# Esquema.net
KiCad netlist of a schematic drawn in EAGLE
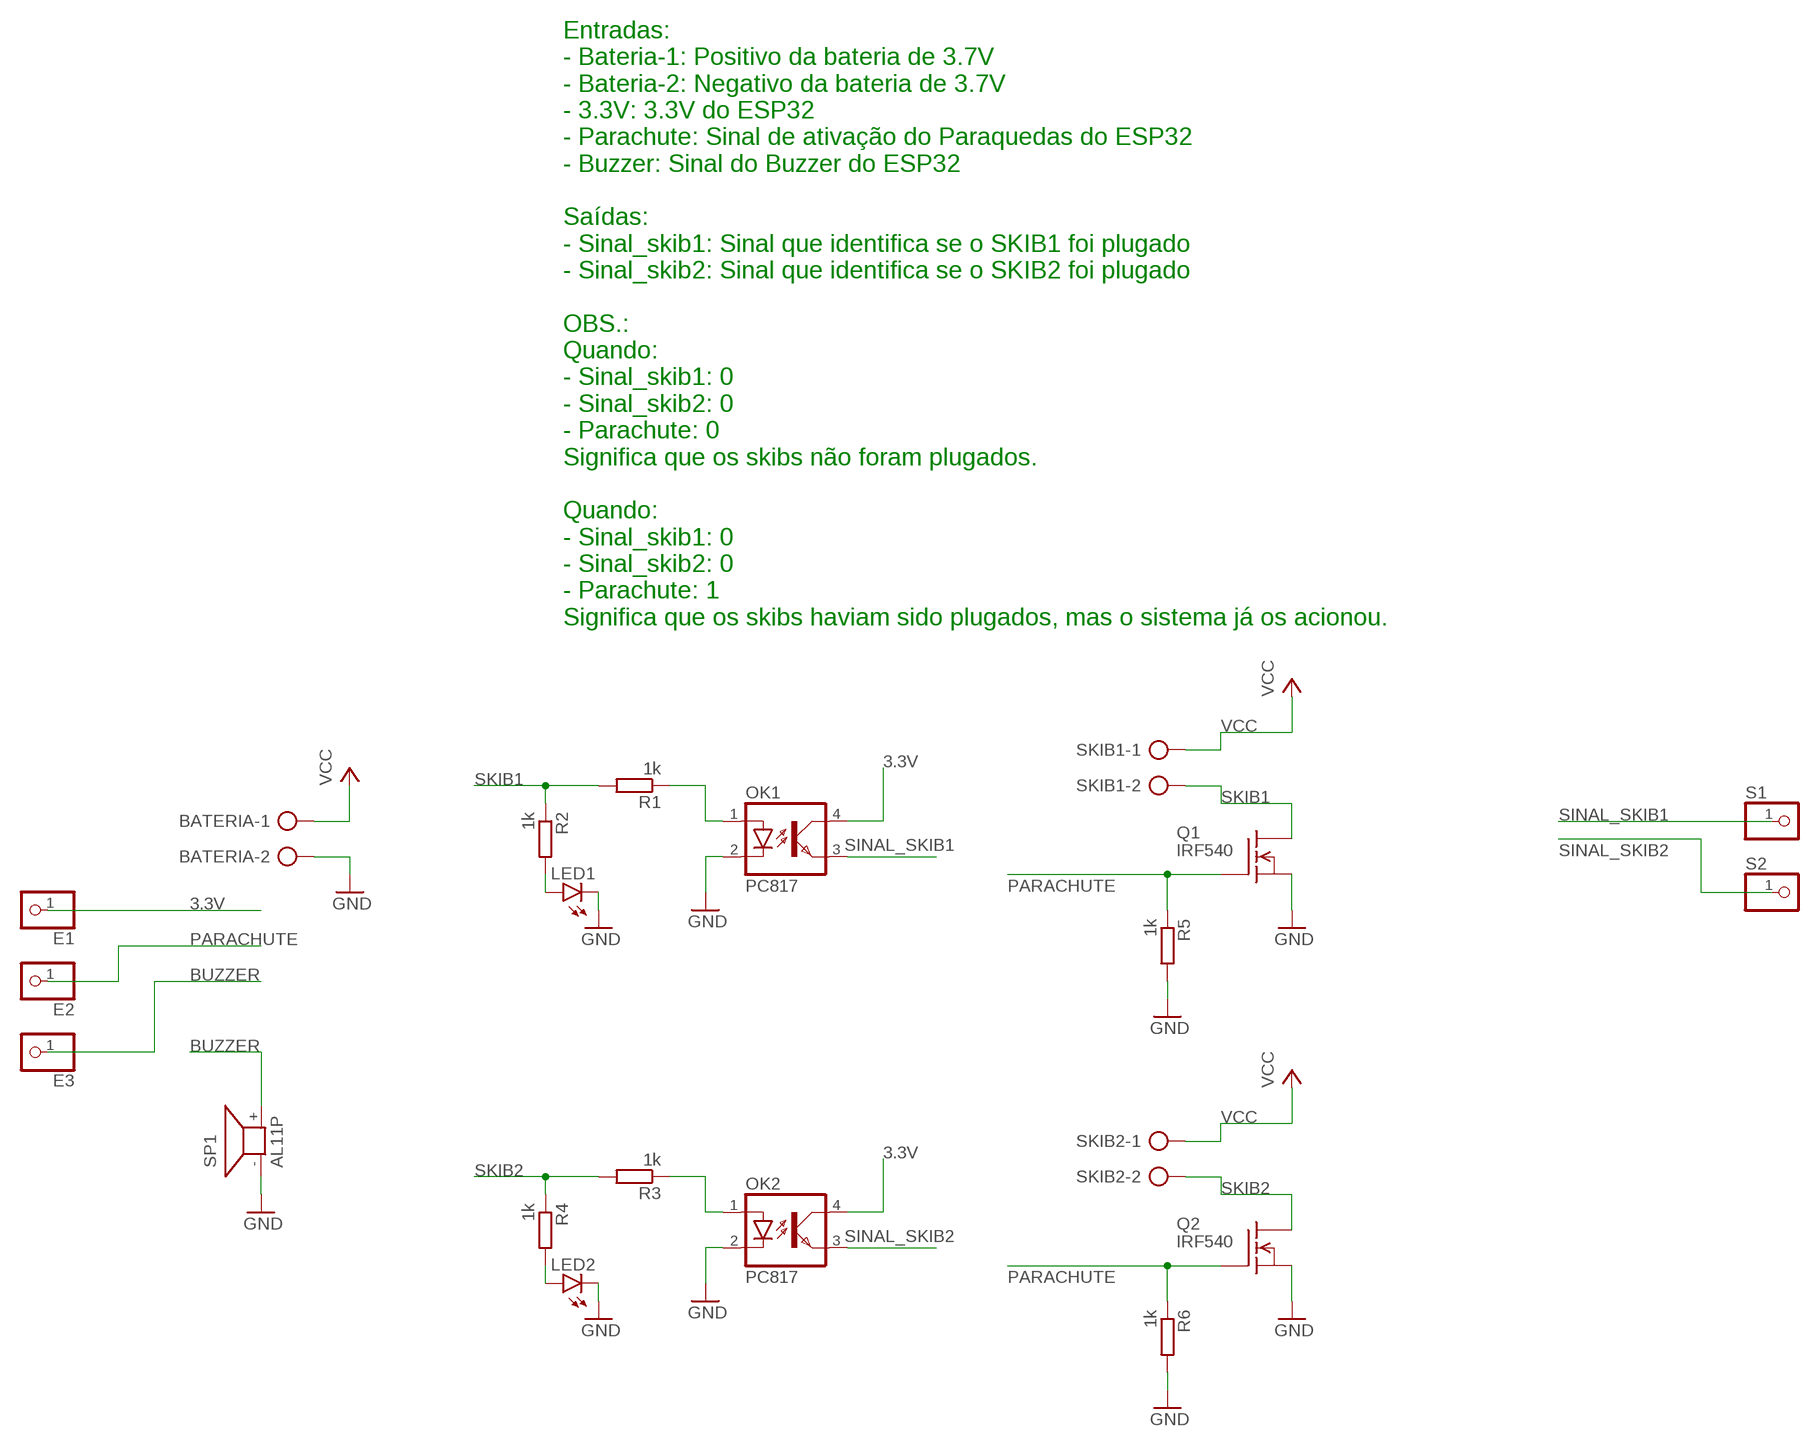
[diagram p0: schematic, sheet 1]

(export (version "E")
  (design (tool "Eeschema 10.0.6"))
  (components
    (comp (ref "BATERIA")
      (value "AK500/2-H")
      (footprint "eagle-import:AK500_2-H")
      (libsource (lib "eagle-import") (part "AK500/2-H"))
    )
    (comp (ref "E1")
      (value "PINHD-1X1")
      (footprint "eagle-import:1X01")
      (libsource (lib "eagle-import") (part "PINHD-1X1"))
    )
    (comp (ref "E2")
      (value "PINHD-1X1")
      (footprint "eagle-import:1X01")
      (libsource (lib "eagle-import") (part "PINHD-1X1"))
    )
    (comp (ref "E3")
      (value "PINHD-1X1")
      (footprint "eagle-import:1X01")
      (libsource (lib "eagle-import") (part "PINHD-1X1"))
    )
    (comp (ref "LED1")
      (value "LED5MM")
      (footprint "eagle-import:LED5MM")
      (libsource (lib "eagle-import") (part "LED5MM"))
    )
    (comp (ref "LED2")
      (value "LED5MM")
      (footprint "eagle-import:LED5MM")
      (libsource (lib "eagle-import") (part "LED5MM"))
    )
    (comp (ref "OK1")
      (value "PC817")
      (footprint "eagle-import:DIL04")
      (fields (field (name "MPN") "PC817X4J000F"))
      (libsource (lib "eagle-import") (part "PC817"))
    )
    (comp (ref "OK2")
      (value "PC817")
      (footprint "eagle-import:DIL04")
      (fields (field (name "MPN") "PC817X4J000F"))
      (libsource (lib "eagle-import") (part "PC817"))
    )
    (comp (ref "Q1")
      (value "IRF540")
      (footprint "eagle-import:TO220")
      (libsource (lib "eagle-import") (part "IRF540"))
    )
    (comp (ref "Q2")
      (value "IRF540")
      (footprint "eagle-import:TO220")
      (libsource (lib "eagle-import") (part "IRF540"))
    )
    (comp (ref "R1")
      (value "1k")
      (footprint "eagle-import:0207_10")
      (libsource (lib "eagle-import") (part "R-EU_0207/10"))
    )
    (comp (ref "R2")
      (value "1k")
      (footprint "eagle-import:0207_10")
      (libsource (lib "eagle-import") (part "R-EU_0207/10"))
    )
    (comp (ref "R3")
      (value "1k")
      (footprint "eagle-import:0207_10")
      (libsource (lib "eagle-import") (part "R-EU_0207/10"))
    )
    (comp (ref "R4")
      (value "1k")
      (footprint "eagle-import:0207_10")
      (libsource (lib "eagle-import") (part "R-EU_0207/10"))
    )
    (comp (ref "R5")
      (value "1k")
      (footprint "eagle-import:0207_10")
      (libsource (lib "eagle-import") (part "R-EU_0207/10"))
    )
    (comp (ref "R6")
      (value "1k")
      (footprint "eagle-import:0207_10")
      (libsource (lib "eagle-import") (part "R-EU_0207/10"))
    )
    (comp (ref "S1")
      (value "PINHD-1X1")
      (footprint "eagle-import:1X01")
      (libsource (lib "eagle-import") (part "PINHD-1X1"))
    )
    (comp (ref "S2")
      (value "PINHD-1X1")
      (footprint "eagle-import:1X01")
      (libsource (lib "eagle-import") (part "PINHD-1X1"))
    )
    (comp (ref "SKIB1")
      (value "AK500/2-H")
      (footprint "eagle-import:AK500_2-H")
      (libsource (lib "eagle-import") (part "AK500/2-H"))
    )
    (comp (ref "SKIB2")
      (value "AK500/2-H")
      (footprint "eagle-import:AK500_2-H")
      (libsource (lib "eagle-import") (part "AK500/2-H"))
    )
    (comp (ref "SP1")
      (value "AL11P")
      (footprint "eagle-import:AL11P")
      (libsource (lib "eagle-import") (part "AL11P"))
    )
  )
  (nets
    (net (code "1") (name "/3.3V") (class "Default")
      (node (ref "E1") (pin "1") (pinfunction "1_1") (pintype "passive"))
      (node (ref "OK1") (pin "4") (pinfunction "COL_4") (pintype "passive"))
      (node (ref "OK2") (pin "4") (pinfunction "COL_4") (pintype "passive"))
    )
    (net (code "2") (name "/BUZZER") (class "Default")
      (node (ref "E3") (pin "1") (pinfunction "1_1") (pintype "passive"))
      (node (ref "SP1") (pin "+") (pinfunction "2_+") (pintype "passive"))
    )
    (net (code "3") (name "/PARACHUTE") (class "Default")
      (node (ref "E2") (pin "1") (pinfunction "1_1") (pintype "passive"))
      (node (ref "Q1") (pin "1") (pinfunction "G_1") (pintype "passive"))
      (node (ref "Q2") (pin "1") (pinfunction "G_1") (pintype "passive"))
      (node (ref "R5") (pin "1") (pinfunction "1_1") (pintype "passive"))
      (node (ref "R6") (pin "1") (pinfunction "1_1") (pintype "passive"))
    )
    (net (code "4") (name "/SINAL_SKIB1") (class "Default")
      (node (ref "OK1") (pin "3") (pinfunction "EMIT_3") (pintype "passive"))
      (node (ref "S1") (pin "1") (pinfunction "1_1") (pintype "passive"))
    )
    (net (code "5") (name "/SINAL_SKIB2") (class "Default")
      (node (ref "OK2") (pin "3") (pinfunction "EMIT_3") (pintype "passive"))
      (node (ref "S2") (pin "1") (pinfunction "1_1") (pintype "passive"))
    )
    (net (code "6") (name "/SKIB1") (class "Default")
      (node (ref "Q1") (pin "2") (pinfunction "D_2") (pintype "passive"))
      (node (ref "R1") (pin "2") (pinfunction "2_2") (pintype "passive"))
      (node (ref "R2") (pin "1") (pinfunction "1_1") (pintype "passive"))
      (node (ref "SKIB1") (pin "2") (pinfunction "KL_2") (pintype "passive"))
    )
    (net (code "7") (name "/SKIB2") (class "Default")
      (node (ref "Q2") (pin "2") (pinfunction "D_2") (pintype "passive"))
      (node (ref "R3") (pin "2") (pinfunction "2_2") (pintype "passive"))
      (node (ref "R4") (pin "1") (pinfunction "1_1") (pintype "passive"))
      (node (ref "SKIB2") (pin "2") (pinfunction "KL_2") (pintype "passive"))
    )
    (net (code "8") (name "GND") (class "Default")
      (node (ref "BATERIA") (pin "2") (pinfunction "KL_2") (pintype "passive"))
      (node (ref "LED1") (pin "K") (pinfunction "C_K") (pintype "passive"))
      (node (ref "LED2") (pin "K") (pinfunction "C_K") (pintype "passive"))
      (node (ref "OK1") (pin "2") (pinfunction "C_2") (pintype "passive"))
      (node (ref "OK2") (pin "2") (pinfunction "C_2") (pintype "passive"))
      (node (ref "Q1") (pin "3") (pinfunction "S_3") (pintype "passive"))
      (node (ref "Q2") (pin "3") (pinfunction "S_3") (pintype "passive"))
      (node (ref "R5") (pin "2") (pinfunction "2_2") (pintype "passive"))
      (node (ref "R6") (pin "2") (pinfunction "2_2") (pintype "passive"))
      (node (ref "SP1") (pin "-") (pinfunction "1_-") (pintype "passive"))
    )
    (net (code "9") (name "Net-(LED1-PadA)") (class "Default")
      (node (ref "LED1") (pin "A") (pinfunction "A_A") (pintype "passive"))
      (node (ref "R2") (pin "2") (pinfunction "2_2") (pintype "passive"))
    )
    (net (code "10") (name "Net-(LED2-PadA)") (class "Default")
      (node (ref "LED2") (pin "A") (pinfunction "A_A") (pintype "passive"))
      (node (ref "R4") (pin "2") (pinfunction "2_2") (pintype "passive"))
    )
    (net (code "11") (name "Net-(OK1-A)") (class "Default")
      (node (ref "OK1") (pin "1") (pinfunction "A_1") (pintype "passive"))
      (node (ref "R1") (pin "1") (pinfunction "1_1") (pintype "passive"))
    )
    (net (code "12") (name "Net-(OK2-A)") (class "Default")
      (node (ref "OK2") (pin "1") (pinfunction "A_1") (pintype "passive"))
      (node (ref "R3") (pin "1") (pinfunction "1_1") (pintype "passive"))
    )
    (net (code "13") (name "VCC") (class "Default")
      (node (ref "BATERIA") (pin "1") (pinfunction "KL_1") (pintype "passive"))
      (node (ref "SKIB1") (pin "1") (pinfunction "KL_1") (pintype "passive"))
      (node (ref "SKIB2") (pin "1") (pinfunction "KL_1") (pintype "passive"))
    )
  )
)
